# Power_Distribution_-_Power_Path_3_Parall.net
KiCad netlist of a schematic drawn in Altium Designer
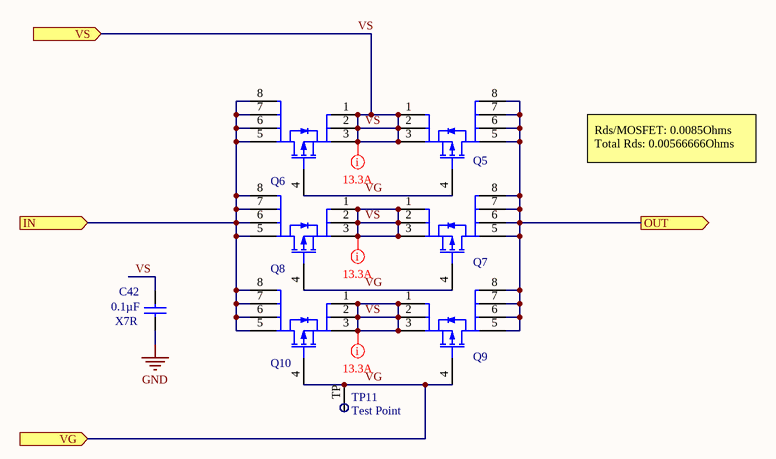
[diagram p0: Power Distribution - Power Path 3 Parallel MOSFET.SchDoc]

(export (version "E")
  (design (tool "Eeschema 10.0.6"))
  (components
    (comp (ref "C42")
      (value "CAP CER 0.1UF 50V 10% X7R 0603")
      (footprint "CAP, 0603")
      (description "0.10µF ±10% 50V Ceramic Capacitor X7R 0603 (1608 Metric)")
      (fields
        (field (name "TOLERANCE") "±10%")
        (field (name "CAPACITANCE") "0.1µF")
        (field (name "TEMPERATURE COEFFICIENT") "X7R")
        (field (name "VOLTAGE") "50V")
      )
      (libsource (lib "Schematic Diagrams") (part "CAP CER 0.1UF 50V 10% X7R 0603"))
    )
    (comp (ref "Q5")
      (value "MOSFET P-CH PWR56 40V 4.9 MOHM")
      (footprint "PMOS PWR56 40V 4.9 MOHM")
      (description "P-Channel 16V 2.5A (Ta) 650mW (Ta) Surface Mount X2-DFN2015-3")
      (libsource (lib "Schematic Diagrams") (part "MOSFET P-CH PWR56 40V 4.9 MOHM"))
    )
    (comp (ref "Q6")
      (value "MOSFET P-CH PWR56 40V 4.9 MOHM")
      (footprint "PMOS PWR56 40V 4.9 MOHM")
      (description "P-Channel 16V 2.5A (Ta) 650mW (Ta) Surface Mount X2-DFN2015-3")
      (libsource (lib "Schematic Diagrams") (part "MOSFET P-CH PWR56 40V 4.9 MOHM"))
    )
    (comp (ref "Q7")
      (value "MOSFET P-CH PWR56 40V 4.9 MOHM")
      (footprint "PMOS PWR56 40V 4.9 MOHM")
      (description "P-Channel 16V 2.5A (Ta) 650mW (Ta) Surface Mount X2-DFN2015-3")
      (libsource (lib "Schematic Diagrams") (part "MOSFET P-CH PWR56 40V 4.9 MOHM"))
    )
    (comp (ref "Q8")
      (value "MOSFET P-CH PWR56 40V 4.9 MOHM")
      (footprint "PMOS PWR56 40V 4.9 MOHM")
      (description "P-Channel 16V 2.5A (Ta) 650mW (Ta) Surface Mount X2-DFN2015-3")
      (libsource (lib "Schematic Diagrams") (part "MOSFET P-CH PWR56 40V 4.9 MOHM"))
    )
    (comp (ref "Q9")
      (value "MOSFET P-CH PWR56 40V 4.9 MOHM")
      (footprint "PMOS PWR56 40V 4.9 MOHM")
      (description "P-Channel 16V 2.5A (Ta) 650mW (Ta) Surface Mount X2-DFN2015-3")
      (libsource (lib "Schematic Diagrams") (part "MOSFET P-CH PWR56 40V 4.9 MOHM"))
    )
    (comp (ref "Q10")
      (value "MOSFET P-CH PWR56 40V 4.9 MOHM")
      (footprint "PMOS PWR56 40V 4.9 MOHM")
      (description "P-Channel 16V 2.5A (Ta) 650mW (Ta) Surface Mount X2-DFN2015-3")
      (libsource (lib "Schematic Diagrams") (part "MOSFET P-CH PWR56 40V 4.9 MOHM"))
    )
    (comp (ref "TP11")
      (value "Test Point")
      (footprint "Test Point")
      (libsource (lib "Schematic Diagrams") (part "Test Point"))
    )
  )
  (nets
    (net (code "1") (name "/IN") (class "Default")
      (node (ref "Q10") (pin "5") (pinfunction "D_5") (pintype "passive"))
      (node (ref "Q10") (pin "6") (pinfunction "D_6") (pintype "passive"))
      (node (ref "Q10") (pin "7") (pinfunction "D_7") (pintype "passive"))
      (node (ref "Q10") (pin "8") (pinfunction "D_8") (pintype "passive"))
      (node (ref "Q6") (pin "5") (pinfunction "D_5") (pintype "passive"))
      (node (ref "Q6") (pin "6") (pinfunction "D_6") (pintype "passive"))
      (node (ref "Q6") (pin "7") (pinfunction "D_7") (pintype "passive"))
      (node (ref "Q6") (pin "8") (pinfunction "D_8") (pintype "passive"))
      (node (ref "Q8") (pin "5") (pinfunction "D_5") (pintype "passive"))
      (node (ref "Q8") (pin "6") (pinfunction "D_6") (pintype "passive"))
      (node (ref "Q8") (pin "7") (pinfunction "D_7") (pintype "passive"))
      (node (ref "Q8") (pin "8") (pinfunction "D_8") (pintype "passive"))
    )
    (net (code "2") (name "/OUT") (class "Default")
      (node (ref "Q5") (pin "5") (pinfunction "D_5") (pintype "passive"))
      (node (ref "Q5") (pin "6") (pinfunction "D_6") (pintype "passive"))
      (node (ref "Q5") (pin "7") (pinfunction "D_7") (pintype "passive"))
      (node (ref "Q5") (pin "8") (pinfunction "D_8") (pintype "passive"))
      (node (ref "Q7") (pin "5") (pinfunction "D_5") (pintype "passive"))
      (node (ref "Q7") (pin "6") (pinfunction "D_6") (pintype "passive"))
      (node (ref "Q7") (pin "7") (pinfunction "D_7") (pintype "passive"))
      (node (ref "Q7") (pin "8") (pinfunction "D_8") (pintype "passive"))
      (node (ref "Q9") (pin "5") (pinfunction "D_5") (pintype "passive"))
      (node (ref "Q9") (pin "6") (pinfunction "D_6") (pintype "passive"))
      (node (ref "Q9") (pin "7") (pinfunction "D_7") (pintype "passive"))
      (node (ref "Q9") (pin "8") (pinfunction "D_8") (pintype "passive"))
    )
    (net (code "3") (name "/VG") (class "Default")
      (node (ref "Q10") (pin "4") (pinfunction "G_4") (pintype "passive"))
      (node (ref "Q5") (pin "4") (pinfunction "G_4") (pintype "passive"))
      (node (ref "Q6") (pin "4") (pinfunction "G_4") (pintype "passive"))
      (node (ref "Q7") (pin "4") (pinfunction "G_4") (pintype "passive"))
      (node (ref "Q8") (pin "4") (pinfunction "G_4") (pintype "passive"))
      (node (ref "Q9") (pin "4") (pinfunction "G_4") (pintype "passive"))
      (node (ref "TP11") (pin "TP") (pinfunction "1_TP") (pintype "passive"))
    )
    (net (code "4") (name "/VS") (class "Default")
      (node (ref "C42") (pin "1") (pinfunction "1_1") (pintype "passive"))
      (node (ref "Q10") (pin "1") (pinfunction "S_1") (pintype "passive"))
      (node (ref "Q10") (pin "2") (pinfunction "S_2") (pintype "passive"))
      (node (ref "Q10") (pin "3") (pinfunction "S_3") (pintype "passive"))
      (node (ref "Q5") (pin "1") (pinfunction "S_1") (pintype "passive"))
      (node (ref "Q5") (pin "2") (pinfunction "S_2") (pintype "passive"))
      (node (ref "Q5") (pin "3") (pinfunction "S_3") (pintype "passive"))
      (node (ref "Q6") (pin "1") (pinfunction "S_1") (pintype "passive"))
      (node (ref "Q6") (pin "2") (pinfunction "S_2") (pintype "passive"))
      (node (ref "Q6") (pin "3") (pinfunction "S_3") (pintype "passive"))
      (node (ref "Q7") (pin "1") (pinfunction "S_1") (pintype "passive"))
      (node (ref "Q7") (pin "2") (pinfunction "S_2") (pintype "passive"))
      (node (ref "Q7") (pin "3") (pinfunction "S_3") (pintype "passive"))
      (node (ref "Q8") (pin "1") (pinfunction "S_1") (pintype "passive"))
      (node (ref "Q8") (pin "2") (pinfunction "S_2") (pintype "passive"))
      (node (ref "Q8") (pin "3") (pinfunction "S_3") (pintype "passive"))
      (node (ref "Q9") (pin "1") (pinfunction "S_1") (pintype "passive"))
      (node (ref "Q9") (pin "2") (pinfunction "S_2") (pintype "passive"))
      (node (ref "Q9") (pin "3") (pinfunction "S_3") (pintype "passive"))
    )
    (net (code "5") (name "GND") (class "Default")
      (node (ref "C42") (pin "2") (pinfunction "2_2") (pintype "passive"))
    )
  )
)
